# MAX3232.net
KiCad netlist of a schematic drawn in Altium Designer
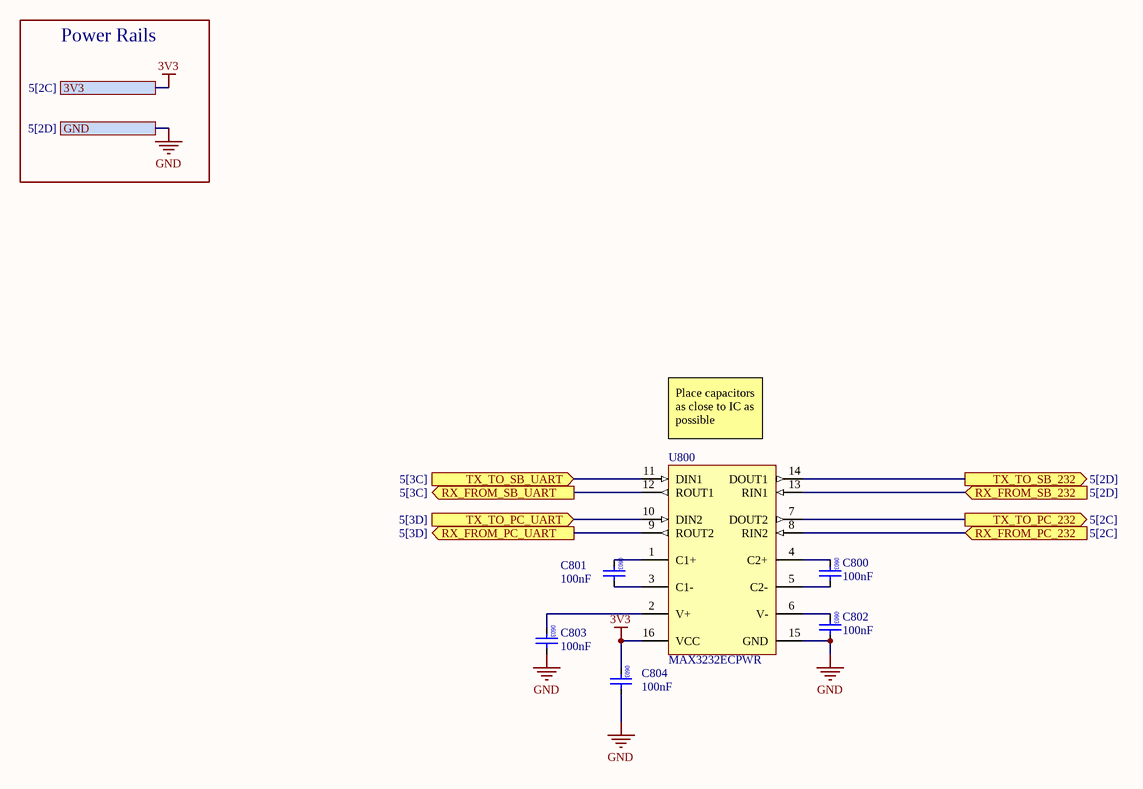
[diagram p0: MAX3232.SchDoc]

(export (version "E")
  (design (tool "Eeschema 10.0.6"))
  (components
    (comp (ref "C800")
      (value "100nF")
      (footprint "0603 Capacitor Footprint")
      (description "CAP CER 0.1UF 50V X7R 0603")
      (fields (field (name "MANUFACTURER PART NUMBER") "CC0603JPX7R9BB104") (field (name "TOLERANCE") "5%"))
      (libsource (lib "UBC Formula Electric") (part "0603 Generic Ceramic Capacitor"))
    )
    (comp (ref "C801")
      (value "100nF")
      (footprint "0603 Capacitor Footprint")
      (description "CAP CER 0.1UF 50V X7R 0603")
      (fields (field (name "MANUFACTURER PART NUMBER") "CC0603JPX7R9BB104") (field (name "TOLERANCE") "5%"))
      (libsource (lib "UBC Formula Electric") (part "0603 Generic Ceramic Capacitor"))
    )
    (comp (ref "C802")
      (value "100nF")
      (footprint "0603 Capacitor Footprint")
      (description "CAP CER 0.1UF 50V X7R 0603")
      (fields (field (name "MANUFACTURER PART NUMBER") "CC0603JPX7R9BB104") (field (name "TOLERANCE") "5%"))
      (libsource (lib "UBC Formula Electric") (part "0603 Generic Ceramic Capacitor"))
    )
    (comp (ref "C803")
      (value "100nF")
      (footprint "0603 Capacitor Footprint")
      (description "CAP CER 0.1UF 50V X7R 0603")
      (fields (field (name "MANUFACTURER PART NUMBER") "CC0603JPX7R9BB104") (field (name "TOLERANCE") "5%"))
      (libsource (lib "UBC Formula Electric") (part "0603 Generic Ceramic Capacitor"))
    )
    (comp (ref "C804")
      (value "100nF")
      (footprint "0603 Capacitor Footprint")
      (description "CAP CER 0.1UF 50V X7R 0603")
      (fields (field (name "MANUFACTURER PART NUMBER") "CC0603JPX7R9BB104") (field (name "TOLERANCE") "5%"))
      (libsource (lib "UBC Formula Electric") (part "0603 Generic Ceramic Capacitor"))
    )
    (comp (ref "U800")
      (value "MAX3232ECPWR")
      (footprint "PW0016A_M")
      (libsource (lib "Altium Content Vault") (part "TI-MAX3232E-TSSOP_PW-16"))
    )
  )
  (nets
    (net (code "1") (name "/RX_FROM_PC_232") (class "Default")
      (node (ref "U800") (pin "8") (pinfunction "RIN2_8") (pintype "input"))
    )
    (net (code "2") (name "/RX_FROM_PC_UART") (class "Default")
      (node (ref "U800") (pin "9") (pinfunction "ROUT2_9") (pintype "output"))
    )
    (net (code "3") (name "/RX_FROM_SB_232") (class "Default")
      (node (ref "U800") (pin "13") (pinfunction "RIN1_13") (pintype "input"))
    )
    (net (code "4") (name "/RX_FROM_SB_UART") (class "Default")
      (node (ref "U800") (pin "12") (pinfunction "ROUT1_12") (pintype "output"))
    )
    (net (code "5") (name "/TX_TO_PC_232") (class "Default")
      (node (ref "U800") (pin "7") (pinfunction "DOUT2_7") (pintype "output"))
    )
    (net (code "6") (name "/TX_TO_PC_UART") (class "Default")
      (node (ref "U800") (pin "10") (pinfunction "DIN2_10") (pintype "input"))
    )
    (net (code "7") (name "/TX_TO_SB_232") (class "Default")
      (node (ref "U800") (pin "14") (pinfunction "DOUT1_14") (pintype "output"))
    )
    (net (code "8") (name "/TX_TO_SB_UART") (class "Default")
      (node (ref "U800") (pin "11") (pinfunction "DIN1_11") (pintype "input"))
    )
    (net (code "9") (name "3V3") (class "Default")
      (node (ref "C804") (pin "2") (pinfunction "2_2") (pintype "passive"))
      (node (ref "U800") (pin "16") (pinfunction "VCC_16") (pintype "power_in"))
    )
    (net (code "10") (name "GND") (class "Default")
      (node (ref "C802") (pin "1") (pinfunction "1_1") (pintype "passive"))
      (node (ref "C803") (pin "1") (pinfunction "1_1") (pintype "passive"))
      (node (ref "C804") (pin "1") (pinfunction "1_1") (pintype "passive"))
      (node (ref "U800") (pin "15") (pinfunction "GND_15") (pintype "power_in"))
    )
    (net (code "11") (name "Net-(U800-C1+)") (class "Default")
      (node (ref "C801") (pin "2") (pinfunction "2_2") (pintype "passive"))
      (node (ref "U800") (pin "1") (pinfunction "C1+_1") (pintype "passive"))
    )
    (net (code "12") (name "Net-(U800-C1-)") (class "Default")
      (node (ref "C801") (pin "1") (pinfunction "1_1") (pintype "passive"))
      (node (ref "U800") (pin "3") (pinfunction "C1-_3") (pintype "passive"))
    )
    (net (code "13") (name "Net-(U800-C2+)") (class "Default")
      (node (ref "C800") (pin "2") (pinfunction "2_2") (pintype "passive"))
      (node (ref "U800") (pin "4") (pinfunction "C2+_4") (pintype "passive"))
    )
    (net (code "14") (name "Net-(U800-C2-)") (class "Default")
      (node (ref "C800") (pin "1") (pinfunction "1_1") (pintype "passive"))
      (node (ref "U800") (pin "5") (pinfunction "C2-_5") (pintype "passive"))
    )
    (net (code "15") (name "Net-(U800-V+)") (class "Default")
      (node (ref "C803") (pin "2") (pinfunction "2_2") (pintype "passive"))
      (node (ref "U800") (pin "2") (pinfunction "V+_2") (pintype "power_in"))
    )
    (net (code "16") (name "Net-(U800-V-)") (class "Default")
      (node (ref "C802") (pin "2") (pinfunction "2_2") (pintype "passive"))
      (node (ref "U800") (pin "6") (pinfunction "V-_6") (pintype "power_in"))
    )
  )
)
